# Adafruit_Ultimate_GPS_FeatherWing.net
KiCad netlist of a schematic drawn in EAGLE
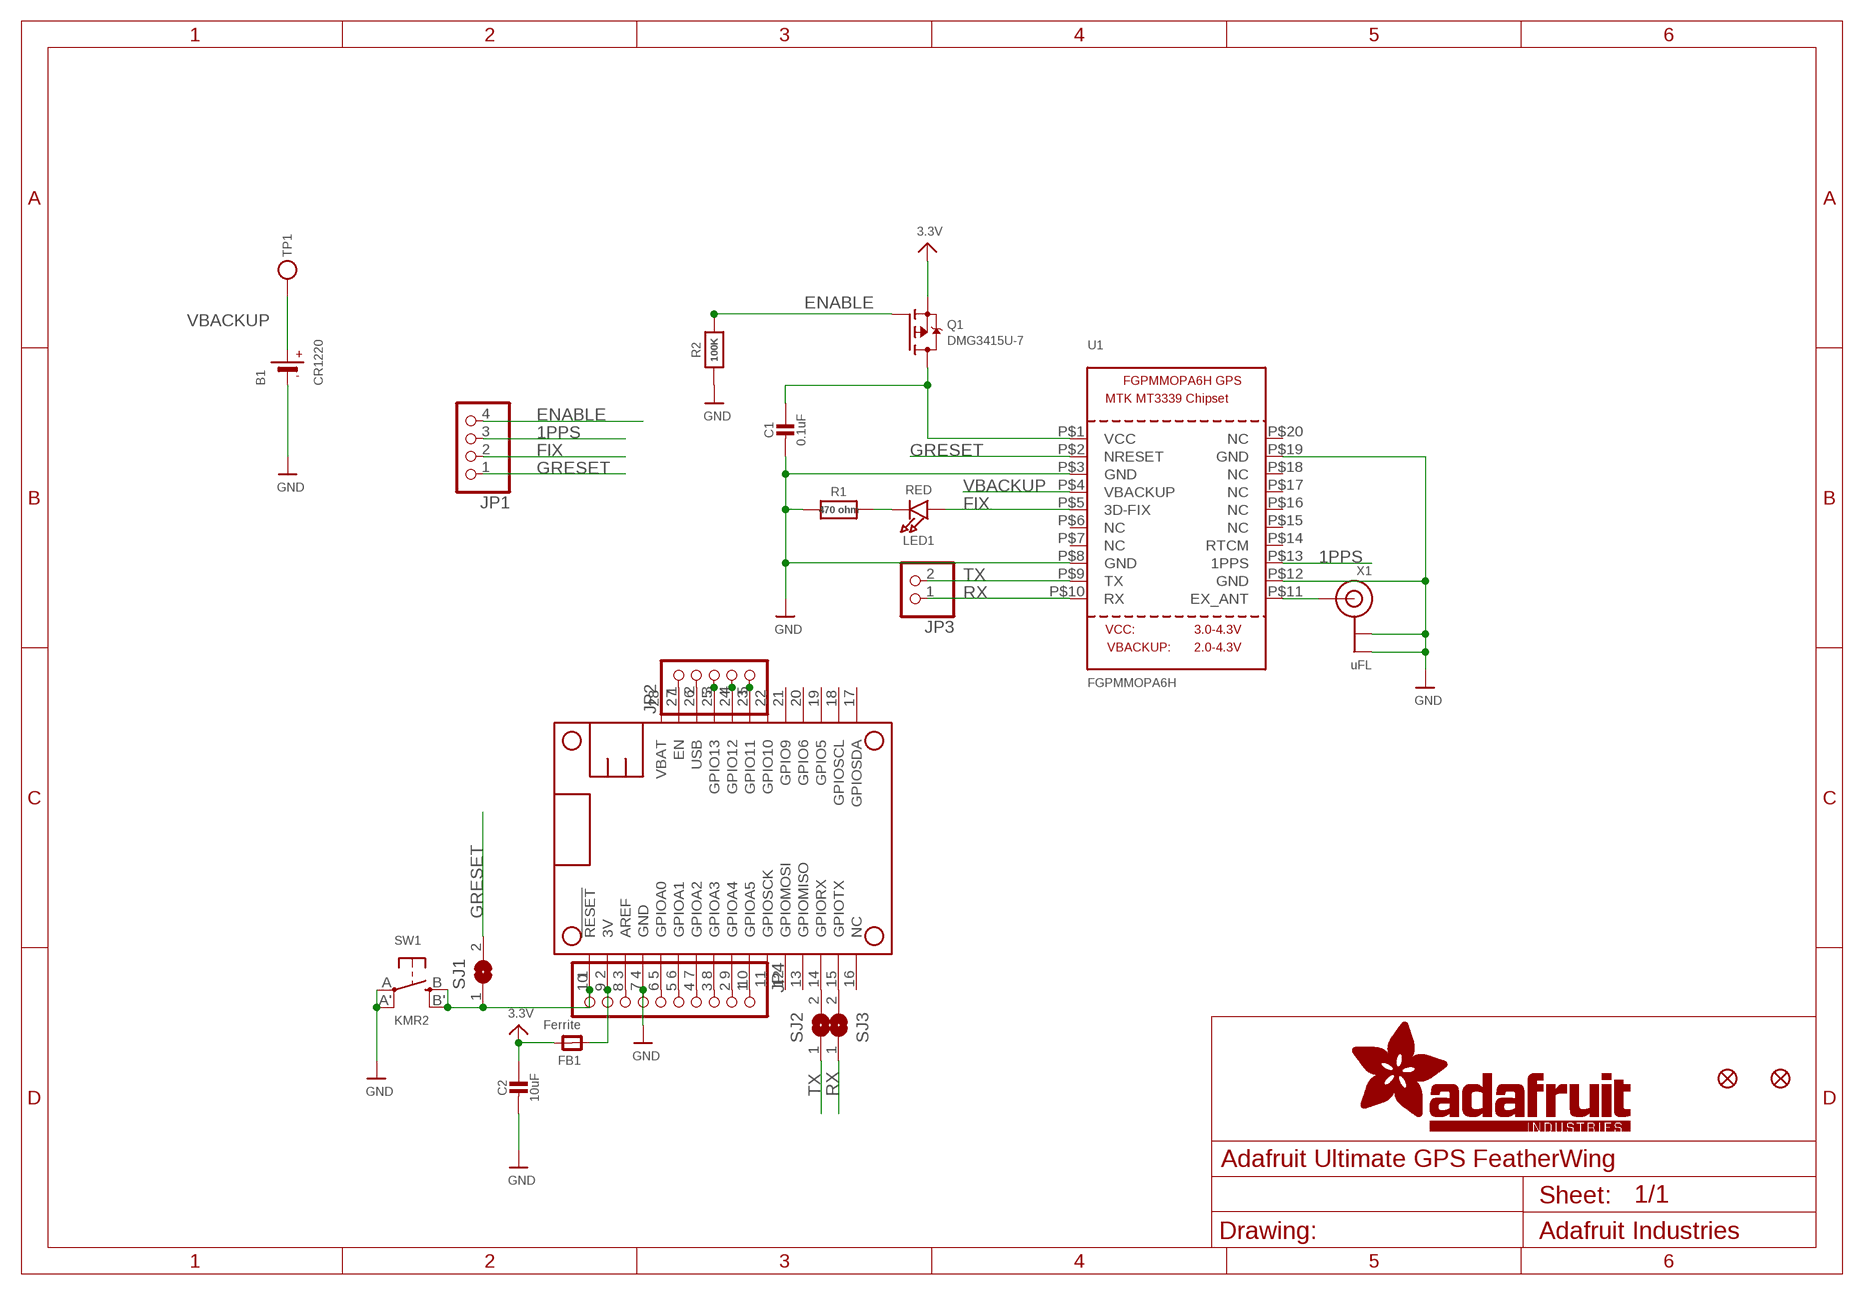
[diagram p0: schematic, sheet 1]

(export (version "E")
  (design (tool "Eeschema 10.0.6"))
  (components
    (comp (ref "B1")
      (value "CR1220")
      (footprint "eagle-import:CR1220-2")
      (libsource (lib "eagle-import") (part "BATTERYCR1220_2"))
    )
    (comp (ref "C1")
      (value "0.1uF")
      (footprint "eagle-import:0805-NO")
      (libsource (lib "eagle-import") (part "CAP_CERAMIC0805-NOOUTLINE"))
    )
    (comp (ref "C2")
      (value "10uF")
      (footprint "eagle-import:0805-NO")
      (libsource (lib "eagle-import") (part "CAP_CERAMIC0805-NOOUTLINE"))
    )
    (comp (ref "FB1")
      (value "Ferrite")
      (footprint "eagle-import:0805-NO")
      (libsource (lib "eagle-import") (part "FERRITE-0805NO"))
    )
    (comp (ref "FID1")
      (value "FIDUCIAL\"\"")
      (footprint "eagle-import:FIDUCIAL_1MM")
      (libsource (lib "eagle-import") (part "FIDUCIAL{dblquote}{dblquote}"))
    )
    (comp (ref "FID2")
      (value "FIDUCIAL\"\"")
      (footprint "eagle-import:FIDUCIAL_1MM")
      (libsource (lib "eagle-import") (part "FIDUCIAL{dblquote}{dblquote}"))
    )
    (comp (ref "JP1")
      (value "HEADER-1X4ROUND")
      (footprint "eagle-import:1X04_ROUND")
      (libsource (lib "eagle-import") (part "HEADER-1X4ROUND"))
    )
    (comp (ref "JP2")
      (value "HEADER-1X570MIL")
      (footprint "eagle-import:1X05_ROUND_70")
      (libsource (lib "eagle-import") (part "HEADER-1X570MIL"))
    )
    (comp (ref "JP3")
      (value "HEADER-1X2ROUND")
      (footprint "eagle-import:1X02_ROUND")
      (libsource (lib "eagle-import") (part "HEADER-1X2ROUND"))
    )
    (comp (ref "JP4")
      (value "HEADER-1X10ROUND")
      (footprint "eagle-import:1X10_ROUND")
      (libsource (lib "eagle-import") (part "HEADER-1X10ROUND"))
    )
    (comp (ref "LED1")
      (value "RED")
      (footprint "eagle-import:CHIPLED_0805_NOOUTLINE")
      (libsource (lib "eagle-import") (part "LED0805_NOOUTLINE"))
    )
    (comp (ref "MS1")
      (value "FEATHERWING")
      (footprint "eagle-import:FEATHERWING")
      (libsource (lib "eagle-import") (part "FEATHERWING"))
    )
    (comp (ref "Q1")
      (value "DMG3415U-7")
      (footprint "eagle-import:SOT23-WIDE")
      (libsource (lib "eagle-import") (part "MOSFET-PWIDE"))
    )
    (comp (ref "R1")
      (value "470 ohm")
      (footprint "eagle-import:0805-NO")
      (libsource (lib "eagle-import") (part "RESISTOR0805_NOOUTLINE"))
    )
    (comp (ref "R2")
      (value "100K")
      (footprint "eagle-import:0805-NO")
      (libsource (lib "eagle-import") (part "RESISTOR0805_NOOUTLINE"))
    )
    (comp (ref "SJ1")
      (value "SOLDERJUMPER")
      (footprint "eagle-import:SOLDERJUMPER_ARROW_NOPASTE")
      (libsource (lib "eagle-import") (part "SOLDERJUMPER"))
    )
    (comp (ref "SJ2")
      (value "SOLDERJUMPERCLOSED")
      (footprint "eagle-import:SOLDERJUMPER_CLOSEDWIRE")
      (libsource (lib "eagle-import") (part "SOLDERJUMPERCLOSED"))
    )
    (comp (ref "SJ3")
      (value "SOLDERJUMPERCLOSED")
      (footprint "eagle-import:SOLDERJUMPER_CLOSEDWIRE")
      (libsource (lib "eagle-import") (part "SOLDERJUMPERCLOSED"))
    )
    (comp (ref "SW1")
      (value "KMR2")
      (footprint "eagle-import:BTN_KMR2_4.6X2.8")
      (libsource (lib "eagle-import") (part "SWITCH_TACT_SMT4.6X2.8"))
    )
    (comp (ref "TP1")
      (value "TESTPOINTROUND1.5MM")
      (footprint "eagle-import:TESTPOINT_ROUND_1.5MM")
      (libsource (lib "eagle-import") (part "TESTPOINTROUND1.5MM"))
    )
    (comp (ref "U1")
      (value "FGPMMOPA6H")
      (footprint "eagle-import:FGPMMOPA6H")
      (libsource (lib "eagle-import") (part "GPS_FGPMMOPA6H"))
    )
    (comp (ref "X1")
      (value "uFL")
      (footprint "eagle-import:U.FL")
      (libsource (lib "eagle-import") (part "ANTENNA_U.FL"))
    )
  )
  (nets
    (net (code "1") (name "/1PPS") (class "Default")
      (node (ref "JP1") (pin "3") (pinfunction "3_3") (pintype "passive"))
      (node (ref "U1") (pin "P$13") (pinfunction "1PPS_P$13") (pintype "bidirectional"))
    )
    (net (code "2") (name "/ENABLE") (class "Default")
      (node (ref "JP1") (pin "4") (pinfunction "4_4") (pintype "passive"))
      (node (ref "Q1") (pin "1") (pinfunction "G_1") (pintype "passive"))
      (node (ref "R2") (pin "2") (pinfunction "2_2") (pintype "passive"))
    )
    (net (code "3") (name "/FIX") (class "Default")
      (node (ref "JP1") (pin "2") (pinfunction "2_2") (pintype "passive"))
      (node (ref "LED1") (pin "A") (pinfunction "A_A") (pintype "passive"))
      (node (ref "U1") (pin "P$5") (pinfunction "3D-FIX_P$5") (pintype "bidirectional"))
    )
    (net (code "4") (name "/GRESET") (class "Default")
      (node (ref "JP1") (pin "1") (pinfunction "1_1") (pintype "passive"))
      (node (ref "SJ1") (pin "2") (pinfunction "2_2") (pintype "passive"))
      (node (ref "U1") (pin "P$2") (pinfunction "NRESET_P$2") (pintype "bidirectional"))
    )
    (net (code "5") (name "/RX") (class "Default")
      (node (ref "JP3") (pin "1") (pinfunction "1_1") (pintype "passive"))
      (node (ref "SJ3") (pin "1") (pinfunction "1_1") (pintype "passive"))
      (node (ref "U1") (pin "P$10") (pinfunction "RX_P$10") (pintype "bidirectional"))
    )
    (net (code "6") (name "/TX") (class "Default")
      (node (ref "JP3") (pin "2") (pinfunction "2_2") (pintype "passive"))
      (node (ref "SJ2") (pin "1") (pinfunction "1_1") (pintype "passive"))
      (node (ref "U1") (pin "P$9") (pinfunction "TX_P$9") (pintype "bidirectional"))
    )
    (net (code "7") (name "/VBACKUP") (class "Default")
      (node (ref "B1") (pin "+") (pinfunction "+_+") (pintype "passive"))
      (node (ref "TP1") (pin "P$1") (pinfunction "P$1_P$1") (pintype "bidirectional"))
      (node (ref "U1") (pin "P$4") (pinfunction "VBACKUP_P$4") (pintype "bidirectional"))
    )
    (net (code "8") (name "/VBAT") (class "Default")
      (node (ref "MS1") (pin "28") (pinfunction "VBAT_28") (pintype "power_in"))
    )
    (net (code "9") (name "3.3V") (class "Default")
      (node (ref "C2") (pin "1") (pinfunction "1_1") (pintype "passive"))
      (node (ref "FB1") (pin "2") (pinfunction "P$2_2") (pintype "passive"))
      (node (ref "Q1") (pin "2") (pinfunction "S_2") (pintype "passive"))
    )
    (net (code "10") (name "GND") (class "Default")
      (node (ref "B1") (pin "-") (pinfunction "-_-") (pintype "passive"))
      (node (ref "C1") (pin "2") (pinfunction "2_2") (pintype "passive"))
      (node (ref "C2") (pin "2") (pinfunction "2_2") (pintype "passive"))
      (node (ref "JP4") (pin "7") (pinfunction "7_7") (pintype "passive"))
      (node (ref "MS1") (pin "4") (pinfunction "GND_4") (pintype "power_in"))
      (node (ref "R1") (pin "1") (pinfunction "1_1") (pintype "passive"))
      (node (ref "R2") (pin "1") (pinfunction "1_1") (pintype "passive"))
      (node (ref "SW1") (pin "A") (pinfunction "P_A") (pintype "passive"))
      (node (ref "SW1") (pin "A'") (pinfunction "P1_A'") (pintype "passive"))
      (node (ref "U1") (pin "P$12") (pinfunction "GND_P$12") (pintype "bidirectional"))
      (node (ref "U1") (pin "P$19") (pinfunction "GND_P$19") (pintype "bidirectional"))
      (node (ref "U1") (pin "P$3") (pinfunction "GND_P$3") (pintype "bidirectional"))
      (node (ref "U1") (pin "P$8") (pinfunction "GND_P$8") (pintype "bidirectional"))
      (node (ref "X1") (pin "1") (pinfunction "GND_1") (pintype "passive"))
      (node (ref "X1") (pin "2") (pinfunction "GND_2") (pintype "passive"))
    )
    (net (code "11") (name "Net-(FB1-P$1)") (class "Default")
      (node (ref "FB1") (pin "1") (pinfunction "P$1_1") (pintype "passive"))
      (node (ref "JP4") (pin "9") (pinfunction "9_9") (pintype "passive"))
      (node (ref "MS1") (pin "2") (pinfunction "3V_2") (pintype "power_in"))
    )
    (net (code "12") (name "Net-(LED1-PadC)") (class "Default")
      (node (ref "LED1") (pin "C") (pinfunction "C_C") (pintype "passive"))
      (node (ref "R1") (pin "2") (pinfunction "2_2") (pintype "passive"))
    )
    (net (code "13") (name "Net-(MS1-AREF)") (class "Default")
      (node (ref "JP4") (pin "8") (pinfunction "8_8") (pintype "passive"))
      (node (ref "MS1") (pin "3") (pinfunction "AREF_3") (pintype "passive"))
    )
    (net (code "14") (name "Net-(MS1-EN)") (class "Default")
      (node (ref "JP2") (pin "1") (pinfunction "1_1") (pintype "passive"))
      (node (ref "MS1") (pin "27") (pinfunction "EN_27") (pintype "passive"))
    )
    (net (code "15") (name "Net-(MS1-GPIO11)") (class "Default")
      (node (ref "JP2") (pin "5") (pinfunction "5_5") (pintype "passive"))
      (node (ref "MS1") (pin "23") (pinfunction "GPIO11_23") (pintype "bidirectional"))
    )
    (net (code "16") (name "Net-(MS1-GPIO12)") (class "Default")
      (node (ref "JP2") (pin "4") (pinfunction "4_4") (pintype "passive"))
      (node (ref "MS1") (pin "24") (pinfunction "GPIO12_24") (pintype "bidirectional"))
    )
    (net (code "17") (name "Net-(MS1-GPIO13)") (class "Default")
      (node (ref "JP2") (pin "3") (pinfunction "3_3") (pintype "passive"))
      (node (ref "MS1") (pin "25") (pinfunction "GPIO13_25") (pintype "bidirectional"))
    )
    (net (code "18") (name "Net-(MS1-GPIOA0)") (class "Default")
      (node (ref "JP4") (pin "6") (pinfunction "6_6") (pintype "passive"))
      (node (ref "MS1") (pin "5") (pinfunction "GPIOA0_5") (pintype "bidirectional"))
    )
    (net (code "19") (name "Net-(MS1-GPIOA1)") (class "Default")
      (node (ref "JP4") (pin "5") (pinfunction "5_5") (pintype "passive"))
      (node (ref "MS1") (pin "6") (pinfunction "GPIOA1_6") (pintype "bidirectional"))
    )
    (net (code "20") (name "Net-(MS1-GPIOA2)") (class "Default")
      (node (ref "JP4") (pin "4") (pinfunction "4_4") (pintype "passive"))
      (node (ref "MS1") (pin "7") (pinfunction "GPIOA2_7") (pintype "bidirectional"))
    )
    (net (code "21") (name "Net-(MS1-GPIOA3)") (class "Default")
      (node (ref "JP4") (pin "3") (pinfunction "3_3") (pintype "passive"))
      (node (ref "MS1") (pin "8") (pinfunction "GPIOA3_8") (pintype "bidirectional"))
    )
    (net (code "22") (name "Net-(MS1-GPIOA4)") (class "Default")
      (node (ref "JP4") (pin "2") (pinfunction "2_2") (pintype "passive"))
      (node (ref "MS1") (pin "9") (pinfunction "GPIOA4_9") (pintype "bidirectional"))
    )
    (net (code "23") (name "Net-(MS1-GPIOA5)") (class "Default")
      (node (ref "JP4") (pin "1") (pinfunction "1_1") (pintype "passive"))
      (node (ref "MS1") (pin "10") (pinfunction "GPIOA5_10") (pintype "bidirectional"))
    )
    (net (code "24") (name "Net-(MS1-GPIORX)") (class "Default")
      (node (ref "MS1") (pin "14") (pinfunction "GPIORX_14") (pintype "bidirectional"))
      (node (ref "SJ2") (pin "2") (pinfunction "2_2") (pintype "passive"))
    )
    (net (code "25") (name "Net-(MS1-GPIOTX)") (class "Default")
      (node (ref "MS1") (pin "15") (pinfunction "GPIOTX_15") (pintype "bidirectional"))
      (node (ref "SJ3") (pin "2") (pinfunction "2_2") (pintype "passive"))
    )
    (net (code "26") (name "Net-(MS1-USB)") (class "Default")
      (node (ref "JP2") (pin "2") (pinfunction "2_2") (pintype "passive"))
      (node (ref "MS1") (pin "26") (pinfunction "USB_26") (pintype "power_in"))
    )
    (net (code "27") (name "Net-(MS1-~{RESET})") (class "Default")
      (node (ref "JP4") (pin "10") (pinfunction "10_10") (pintype "passive"))
      (node (ref "MS1") (pin "1") (pinfunction "~{RESET}_1") (pintype "input"))
      (node (ref "SJ1") (pin "1") (pinfunction "1_1") (pintype "passive"))
      (node (ref "SW1") (pin "B") (pinfunction "S_B") (pintype "passive"))
      (node (ref "SW1") (pin "B'") (pinfunction "S1_B'") (pintype "passive"))
    )
    (net (code "28") (name "Net-(Q1-D)") (class "Default")
      (node (ref "C1") (pin "1") (pinfunction "1_1") (pintype "passive"))
      (node (ref "Q1") (pin "3") (pinfunction "D_3") (pintype "passive"))
      (node (ref "U1") (pin "P$1") (pinfunction "VCC_P$1") (pintype "bidirectional"))
    )
    (net (code "29") (name "Net-(U1-EX_ANT)") (class "Default")
      (node (ref "U1") (pin "P$11") (pinfunction "EX_ANT_P$11") (pintype "bidirectional"))
      (node (ref "X1") (pin "3") (pinfunction "SIGNAL_3") (pintype "passive"))
    )
    (net (code "30") (name "unconnected-(MS1-GPIO5-Pad19)") (class "Default")
      (node (ref "MS1") (pin "19") (pinfunction "GPIO5_19") (pintype "bidirectional"))
    )
    (net (code "31") (name "unconnected-(MS1-GPIO6-Pad20)") (class "Default")
      (node (ref "MS1") (pin "20") (pinfunction "GPIO6_20") (pintype "bidirectional"))
    )
    (net (code "32") (name "unconnected-(MS1-GPIO9-Pad21)") (class "Default")
      (node (ref "MS1") (pin "21") (pinfunction "GPIO9_21") (pintype "bidirectional"))
    )
    (net (code "33") (name "unconnected-(MS1-GPIO10-Pad22)") (class "Default")
      (node (ref "MS1") (pin "22") (pinfunction "GPIO10_22") (pintype "bidirectional"))
    )
    (net (code "34") (name "unconnected-(MS1-GPIOMISO-Pad13)") (class "Default")
      (node (ref "MS1") (pin "13") (pinfunction "GPIOMISO_13") (pintype "bidirectional"))
    )
    (net (code "35") (name "unconnected-(MS1-GPIOMOSI-Pad12)") (class "Default")
      (node (ref "MS1") (pin "12") (pinfunction "GPIOMOSI_12") (pintype "bidirectional"))
    )
    (net (code "36") (name "unconnected-(MS1-GPIOSCK-Pad11)") (class "Default")
      (node (ref "MS1") (pin "11") (pinfunction "GPIOSCK_11") (pintype "bidirectional"))
    )
    (net (code "37") (name "unconnected-(MS1-GPIOSCL-Pad18)") (class "Default")
      (node (ref "MS1") (pin "18") (pinfunction "GPIOSCL_18") (pintype "bidirectional"))
    )
    (net (code "38") (name "unconnected-(MS1-GPIOSDA-Pad17)") (class "Default")
      (node (ref "MS1") (pin "17") (pinfunction "GPIOSDA_17") (pintype "bidirectional"))
    )
    (net (code "39") (name "unconnected-(MS1-NC-Pad16)") (class "Default")
      (node (ref "MS1") (pin "16") (pinfunction "NC_16") (pintype "passive"))
    )
    (net (code "40") (name "unconnected-(U1-NC-PadP$6)") (class "Default")
      (node (ref "U1") (pin "P$6") (pinfunction "NC_P$6") (pintype "bidirectional"))
    )
    (net (code "41") (name "unconnected-(U1-NC-PadP$7)") (class "Default")
      (node (ref "U1") (pin "P$7") (pinfunction "NC_P$7") (pintype "bidirectional"))
    )
    (net (code "42") (name "unconnected-(U1-NC-PadP$15)") (class "Default")
      (node (ref "U1") (pin "P$15") (pinfunction "NC_P$15") (pintype "bidirectional"))
    )
    (net (code "43") (name "unconnected-(U1-NC-PadP$16)") (class "Default")
      (node (ref "U1") (pin "P$16") (pinfunction "NC_P$16") (pintype "bidirectional"))
    )
    (net (code "44") (name "unconnected-(U1-NC-PadP$17)") (class "Default")
      (node (ref "U1") (pin "P$17") (pinfunction "NC_P$17") (pintype "bidirectional"))
    )
    (net (code "45") (name "unconnected-(U1-NC-PadP$18)") (class "Default")
      (node (ref "U1") (pin "P$18") (pinfunction "NC_P$18") (pintype "bidirectional"))
    )
    (net (code "46") (name "unconnected-(U1-NC-PadP$20)") (class "Default")
      (node (ref "U1") (pin "P$20") (pinfunction "NC_P$20") (pintype "bidirectional"))
    )
    (net (code "47") (name "unconnected-(U1-RTCM-PadP$14)") (class "Default")
      (node (ref "U1") (pin "P$14") (pinfunction "RTCM_P$14") (pintype "bidirectional"))
    )
  )
)
